# LAMEBOY.net
KiCad netlist of a schematic drawn in EAGLE
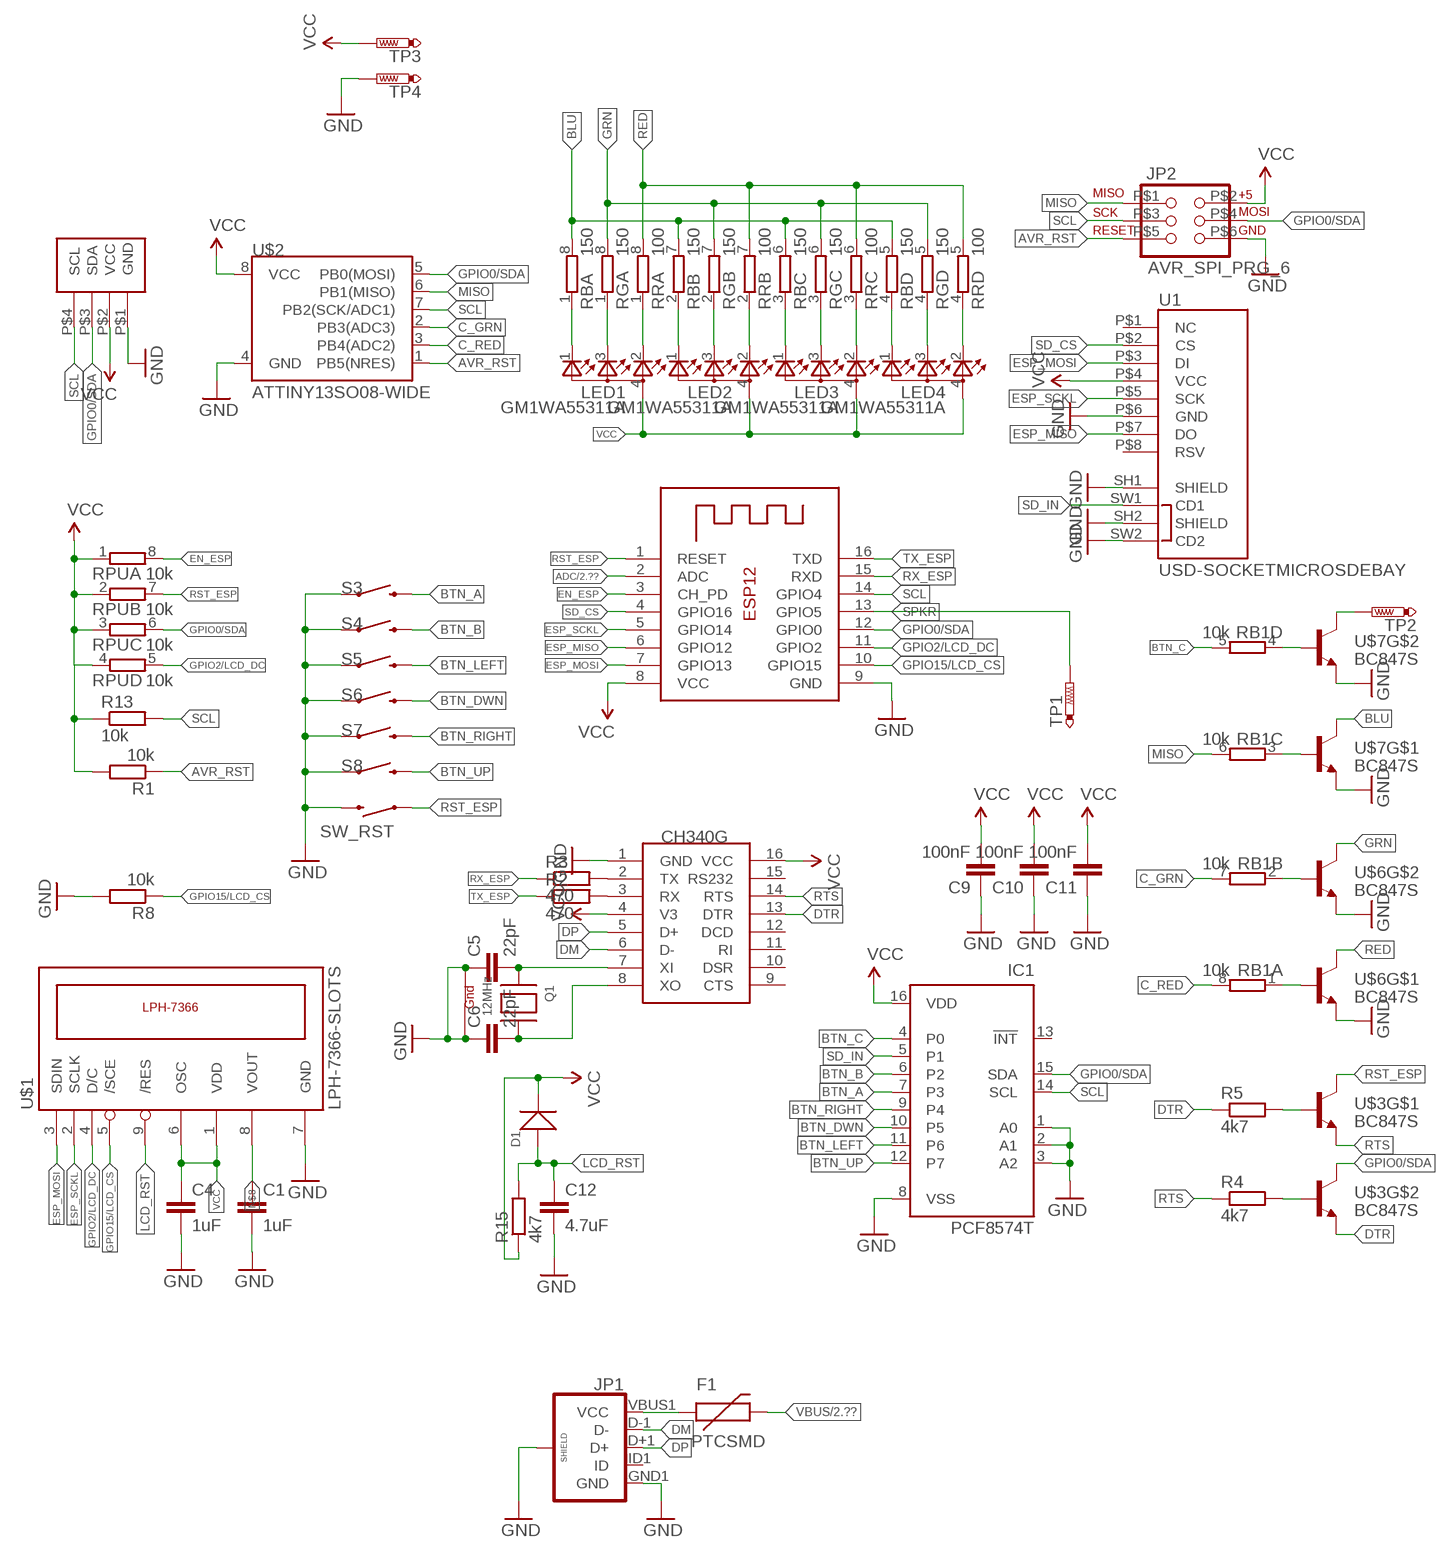
[diagram p0: schematic, sheet 1]
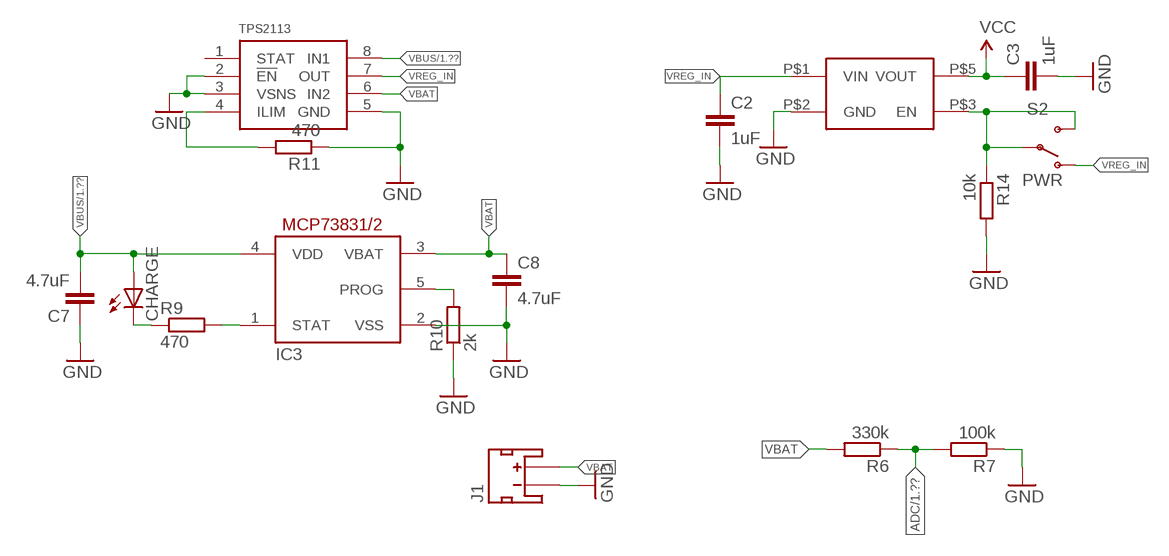
[diagram p1: schematic, sheet 2]

(export (version "E")
  (design (tool "Eeschema 10.0.6"))
  (components
    (comp (ref "C1")
      (value "1uF")
      (footprint "eagle-import:C0805")
      (libsource (lib "eagle-import") (part "C-EUC0805"))
    )
    (comp (ref "C4")
      (value "1uF")
      (footprint "eagle-import:C0805")
      (libsource (lib "eagle-import") (part "C-EUC0805"))
    )
    (comp (ref "C5")
      (value "22pF")
      (footprint "eagle-import:C0805")
      (libsource (lib "eagle-import") (part "C-EUC0805"))
    )
    (comp (ref "C6")
      (value "22pF")
      (footprint "eagle-import:C0805")
      (libsource (lib "eagle-import") (part "C-EUC0805"))
    )
    (comp (ref "C9")
      (value "100nF")
      (footprint "eagle-import:C0805")
      (libsource (lib "eagle-import") (part "C-EUC0805"))
    )
    (comp (ref "C10")
      (value "100nF")
      (footprint "eagle-import:C0805")
      (libsource (lib "eagle-import") (part "C-EUC0805"))
    )
    (comp (ref "C11")
      (value "100nF")
      (footprint "eagle-import:C0805")
      (libsource (lib "eagle-import") (part "C-EUC0805"))
    )
    (comp (ref "C12")
      (value "4.7uF")
      (footprint "eagle-import:C0805")
      (libsource (lib "eagle-import") (part "C-EUC0805"))
    )
    (comp (ref "CH340G")
      (value "CH340GCH340G")
      (footprint "eagle-import:SOIC16")
      (libsource (lib "eagle-import") (part "CH340GCH340G"))
    )
    (comp (ref "D1")
      (value "DIODE'1N4148-SMD'")
      (footprint "eagle-import:LL-34")
      (libsource (lib "eagle-import") (part "DIODE'1N4148-SMD'"))
    )
    (comp (ref "F1")
      (value "PTCSMD")
      (footprint "eagle-import:PTC-1206")
      (libsource (lib "eagle-import") (part "PTCSMD"))
    )
    (comp (ref "IC1")
      (value "PCF8574T")
      (footprint "eagle-import:SO16W")
      (fields (field (name "MPN") "PCF8574T/3,512"))
      (libsource (lib "eagle-import") (part "PCF8574T"))
    )
    (comp (ref "JP1")
      (value "USB_MICROB_PLUG-IDK")
      (footprint "eagle-import:USB-AB-MICRO-SMD_SLOT")
      (libsource (lib "eagle-import") (part "USB_MICROB_PLUG-IDK"))
    )
    (comp (ref "JP2")
      (value "AVR_SPI_PRG_6")
      (footprint "eagle-import:2X3_SMD_PAD")
      (libsource (lib "eagle-import") (part "AVR_SPI_PRG_6"))
    )
    (comp (ref "LED1")
      (value "GM1WA55311A")
      (footprint "eagle-import:GM1WA55311A")
      (libsource (lib "eagle-import") (part "GM1WA55311A"))
    )
    (comp (ref "LED2")
      (value "GM1WA55311A")
      (footprint "eagle-import:GM1WA55311A")
      (libsource (lib "eagle-import") (part "GM1WA55311A"))
    )
    (comp (ref "LED3")
      (value "GM1WA55311A")
      (footprint "eagle-import:GM1WA55311A")
      (libsource (lib "eagle-import") (part "GM1WA55311A"))
    )
    (comp (ref "LED4")
      (value "GM1WA55311A")
      (footprint "eagle-import:GM1WA55311A")
      (libsource (lib "eagle-import") (part "GM1WA55311A"))
    )
    (comp (ref "Q1")
      (value "12MHz")
      (footprint "eagle-import:NX3225_BIGGER")
      (libsource (lib "eagle-import") (part "XTAL-4BIGGER"))
    )
    (comp (ref "R1")
      (value "10k")
      (footprint "eagle-import:R0805")
      (libsource (lib "eagle-import") (part "R-EU_R0805"))
    )
    (comp (ref "R2")
      (value "470")
      (footprint "eagle-import:R0805")
      (libsource (lib "eagle-import") (part "R-EU_R0805"))
    )
    (comp (ref "R3")
      (value "470")
      (footprint "eagle-import:R0805")
      (libsource (lib "eagle-import") (part "R-EU_R0805"))
    )
    (comp (ref "R4")
      (value "4k7")
      (footprint "eagle-import:R0805")
      (libsource (lib "eagle-import") (part "R-EU_R0805"))
    )
    (comp (ref "R5")
      (value "4k7")
      (footprint "eagle-import:R0805")
      (libsource (lib "eagle-import") (part "R-EU_R0805"))
    )
    (comp (ref "R8")
      (value "10k")
      (footprint "eagle-import:R0805")
      (libsource (lib "eagle-import") (part "R-EU_R0805"))
    )
    (comp (ref "R13")
      (value "10k")
      (footprint "eagle-import:R0805")
      (libsource (lib "eagle-import") (part "R-EU_R0805"))
    )
    (comp (ref "R15")
      (value "4k7")
      (footprint "eagle-import:R0805")
      (libsource (lib "eagle-import") (part "R-EU_R0805"))
    )
    (comp (ref "RB")
      (value "150")
      (footprint "eagle-import:0603-ARC")
      (libsource (lib "eagle-import") (part "4R-N0603-ARC"))
    )
    (comp (ref "RB1")
      (value "10k")
      (footprint "eagle-import:0603-ARC")
      (libsource (lib "eagle-import") (part "4R-N0603-ARC"))
    )
    (comp (ref "RG")
      (value "150")
      (footprint "eagle-import:0603-ARC")
      (libsource (lib "eagle-import") (part "4R-N0603-ARC"))
    )
    (comp (ref "RPU")
      (value "10k")
      (footprint "eagle-import:0603-ARC")
      (libsource (lib "eagle-import") (part "4R-N0603-ARC"))
    )
    (comp (ref "RR")
      (value "100")
      (footprint "eagle-import:0603-ARC")
      (libsource (lib "eagle-import") (part "4R-N0603-ARC"))
    )
    (comp (ref "S3")
      (value "SWITCH-MOMENTARY-2SMD-4")
      (footprint "eagle-import:TACTILE_SWITCH_TALL")
      (libsource (lib "eagle-import") (part "SWITCH-MOMENTARY-2SMD-4"))
    )
    (comp (ref "S4")
      (value "SWITCH-MOMENTARY-2SMD-4")
      (footprint "eagle-import:TACTILE_SWITCH_TALL")
      (libsource (lib "eagle-import") (part "SWITCH-MOMENTARY-2SMD-4"))
    )
    (comp (ref "S5")
      (value "SWITCH-MOMENTARY-2SMD-4")
      (footprint "eagle-import:TACTILE_SWITCH_TALL")
      (libsource (lib "eagle-import") (part "SWITCH-MOMENTARY-2SMD-4"))
    )
    (comp (ref "S6")
      (value "SWITCH-MOMENTARY-2SMD-4")
      (footprint "eagle-import:TACTILE_SWITCH_TALL")
      (libsource (lib "eagle-import") (part "SWITCH-MOMENTARY-2SMD-4"))
    )
    (comp (ref "S7")
      (value "SWITCH-MOMENTARY-2SMD-4")
      (footprint "eagle-import:TACTILE_SWITCH_TALL")
      (libsource (lib "eagle-import") (part "SWITCH-MOMENTARY-2SMD-4"))
    )
    (comp (ref "S8")
      (value "SWITCH-MOMENTARY-2SMD-4")
      (footprint "eagle-import:TACTILE_SWITCH_TALL")
      (libsource (lib "eagle-import") (part "SWITCH-MOMENTARY-2SMD-4"))
    )
    (comp (ref "SW_RST")
      (value "SWITCH-MOMENTARY-2-SMD-1101NE")
      (footprint "eagle-import:TACTILE-SWITCH-1101NE")
      (libsource (lib "eagle-import") (part "SWITCH-MOMENTARY-2-SMD-1101NE"))
    )
    (comp (ref "TP1")
      (value "PTR1B1,27")
      (footprint "eagle-import:B1,27")
      (libsource (lib "eagle-import") (part "PTR1B1,27"))
    )
    (comp (ref "TP2")
      (value "PTR1B1,27")
      (footprint "eagle-import:B1,27")
      (libsource (lib "eagle-import") (part "PTR1B1,27"))
    )
    (comp (ref "TP3")
      (value "PTR1B1,27")
      (footprint "eagle-import:B1,27")
      (libsource (lib "eagle-import") (part "PTR1B1,27"))
    )
    (comp (ref "TP4")
      (value "PTR1B1,27")
      (footprint "eagle-import:B1,27")
      (libsource (lib "eagle-import") (part "PTR1B1,27"))
    )
    (comp (ref "U$1")
      (value "LPH-7366-SLOTS")
      (footprint "eagle-import:LPH-7366-SLOTS")
      (libsource (lib "eagle-import") (part "LPH-7366-SLOTS"))
    )
    (comp (ref "U$2")
      (value "ATTINY13SO08-WIDE")
      (footprint "eagle-import:SO08-EIAJ")
      (libsource (lib "eagle-import") (part "ATTINY13SO08-WIDE"))
    )
    (comp (ref "U$3")
      (value "BC847S")
      (footprint "eagle-import:SOT363")
      (libsource (lib "eagle-import") (part "MMDT3904"))
    )
    (comp (ref "U$6")
      (value "BC847S")
      (footprint "eagle-import:SOT363")
      (libsource (lib "eagle-import") (part "MMDT3904"))
    )
    (comp (ref "U$7")
      (value "BC847S")
      (footprint "eagle-import:SOT363")
      (libsource (lib "eagle-import") (part "MMDT3904"))
    )
    (comp (ref "U$10")
      (value "I2C_GROVE")
      (footprint "eagle-import:I2C_GROVE")
      (libsource (lib "eagle-import") (part "I2C_GROVE"))
    )
    (comp (ref "U1")
      (value "USD-SOCKETMICROSDEBAY")
      (footprint "eagle-import:MICRO-SD-SOCKET-EBAY")
      (libsource (lib "eagle-import") (part "USD-SOCKETMICROSDEBAY"))
    )
    (comp (ref "X1")
      (value "ESP-12")
      (footprint "eagle-import:ESP-12")
      (libsource (lib "eagle-import") (part "ESP-12"))
    )
    (comp (ref "C2")
      (value "1uF")
      (footprint "eagle-import:C0805")
      (libsource (lib "eagle-import") (part "C-EUC0805"))
    )
    (comp (ref "C3")
      (value "1uF")
      (footprint "eagle-import:C0805")
      (libsource (lib "eagle-import") (part "C-EUC0805"))
    )
    (comp (ref "C7")
      (value "4.7uF")
      (footprint "eagle-import:C0805")
      (libsource (lib "eagle-import") (part "C-EUC0805"))
    )
    (comp (ref "C8")
      (value "4.7uF")
      (footprint "eagle-import:C0805")
      (libsource (lib "eagle-import") (part "C-EUC0805"))
    )
    (comp (ref "CHARGE")
      (value "LEDCHARLIE")
      (footprint "eagle-import:CHIPLED_0603_CHARLIE")
      (libsource (lib "eagle-import") (part "LEDCHARLIE"))
    )
    (comp (ref "IC3")
      (value "MCP73831")
      (footprint "eagle-import:SOT23-5L")
      (libsource (lib "eagle-import") (part "MCP73831/OT"))
    )
    (comp (ref "J1")
      (value "JST_2MM_MALE")
      (footprint "eagle-import:JST-2-SMD")
      (libsource (lib "eagle-import") (part "JST_2MM_MALE"))
    )
    (comp (ref "R6")
      (value "330k")
      (footprint "eagle-import:R0805")
      (libsource (lib "eagle-import") (part "R-EU_R0805"))
    )
    (comp (ref "R7")
      (value "100k")
      (footprint "eagle-import:R0805")
      (libsource (lib "eagle-import") (part "R-EU_R0805"))
    )
    (comp (ref "R9")
      (value "470")
      (footprint "eagle-import:R0805")
      (libsource (lib "eagle-import") (part "R-EU_R0805"))
    )
    (comp (ref "R10")
      (value "2k")
      (footprint "eagle-import:R0805")
      (libsource (lib "eagle-import") (part "R-EU_R0805"))
    )
    (comp (ref "R11")
      (value "470")
      (footprint "eagle-import:R0805")
      (libsource (lib "eagle-import") (part "R-EU_R0805"))
    )
    (comp (ref "R14")
      (value "10k")
      (footprint "eagle-import:R0805")
      (libsource (lib "eagle-import") (part "R-EU_R0805"))
    )
    (comp (ref "S2")
      (value "PWR")
      (footprint "eagle-import:SWITCH-SPST-SMD-A")
      (libsource (lib "eagle-import") (part "SWITCH-SPDT-SMD-A"))
    )
    (comp (ref "U$4")
      (value "TPS2113-PW")
      (footprint "eagle-import:TEXAS-PW")
      (libsource (lib "eagle-import") (part "TPS2113-PW"))
    )
    (comp (ref "U$9")
      (value "AP2112KAP2112K")
      (footprint "eagle-import:AP2112")
      (libsource (lib "eagle-import") (part "AP2112KAP2112K"))
    )
  )
  (nets
    (net (code "1") (name "ADC") (class "Default")
      (node (ref "R6") (pin "1") (pinfunction "1_1") (pintype "passive"))
      (node (ref "R7") (pin "2") (pinfunction "2_2") (pintype "passive"))
      (node (ref "X1") (pin "2") (pinfunction "ADC_2") (pintype "passive"))
    )
    (net (code "2") (name "AVR_RST") (class "Default")
      (node (ref "JP2") (pin "P$5") (pinfunction "5_P$5") (pintype "passive"))
      (node (ref "R1") (pin "1") (pinfunction "1_1") (pintype "passive"))
      (node (ref "U$2") (pin "1") (pinfunction "PB5(NRES)_1") (pintype "bidirectional"))
    )
    (net (code "3") (name "BLU") (class "Default")
      (node (ref "RB") (pin "5") (pinfunction "2_5") (pintype "passive"))
      (node (ref "RB") (pin "6") (pinfunction "2_6") (pintype "passive"))
      (node (ref "RB") (pin "7") (pinfunction "2_7") (pintype "passive"))
      (node (ref "RB") (pin "8") (pinfunction "2_8") (pintype "passive"))
      (node (ref "U$7") (pin "3") (pinfunction "C_3") (pintype "passive"))
    )
    (net (code "4") (name "BTN_A") (class "Default")
      (node (ref "IC1") (pin "7") (pinfunction "P3_7") (pintype "bidirectional"))
      (node (ref "S3") (pin "B2") (pinfunction "2_B2") (pintype "passive"))
    )
    (net (code "5") (name "BTN_B") (class "Default")
      (node (ref "IC1") (pin "6") (pinfunction "P2_6") (pintype "bidirectional"))
      (node (ref "S4") (pin "B2") (pinfunction "2_B2") (pintype "passive"))
    )
    (net (code "6") (name "BTN_C") (class "Default")
      (node (ref "IC1") (pin "4") (pinfunction "P0_4") (pintype "bidirectional"))
      (node (ref "RB1") (pin "5") (pinfunction "2_5") (pintype "passive"))
    )
    (net (code "7") (name "BTN_DWN") (class "Default")
      (node (ref "IC1") (pin "10") (pinfunction "P5_10") (pintype "bidirectional"))
      (node (ref "S6") (pin "B2") (pinfunction "2_B2") (pintype "passive"))
    )
    (net (code "8") (name "BTN_LEFT") (class "Default")
      (node (ref "IC1") (pin "11") (pinfunction "P6_11") (pintype "bidirectional"))
      (node (ref "S5") (pin "B2") (pinfunction "2_B2") (pintype "passive"))
    )
    (net (code "9") (name "BTN_RIGHT") (class "Default")
      (node (ref "IC1") (pin "9") (pinfunction "P4_9") (pintype "bidirectional"))
      (node (ref "S7") (pin "B2") (pinfunction "2_B2") (pintype "passive"))
    )
    (net (code "10") (name "BTN_UP") (class "Default")
      (node (ref "IC1") (pin "12") (pinfunction "P7_12") (pintype "bidirectional"))
      (node (ref "S8") (pin "B2") (pinfunction "2_B2") (pintype "passive"))
    )
    (net (code "11") (name "C_GRN") (class "Default")
      (node (ref "RB1") (pin "7") (pinfunction "2_7") (pintype "passive"))
      (node (ref "U$2") (pin "2") (pinfunction "PB3(ADC3)_2") (pintype "bidirectional"))
    )
    (net (code "12") (name "C_RED") (class "Default")
      (node (ref "RB1") (pin "8") (pinfunction "2_8") (pintype "passive"))
      (node (ref "U$2") (pin "3") (pinfunction "PB4(ADC2)_3") (pintype "bidirectional"))
    )
    (net (code "13") (name "DM") (class "Default")
      (node (ref "CH340G") (pin "6") (pinfunction "D-_6") (pintype "bidirectional"))
      (node (ref "JP1") (pin "D-1") (pinfunction "D-_D-1") (pintype "bidirectional"))
    )
    (net (code "14") (name "DP") (class "Default")
      (node (ref "CH340G") (pin "5") (pinfunction "D+_5") (pintype "bidirectional"))
      (node (ref "JP1") (pin "D+1") (pinfunction "D+_D+1") (pintype "bidirectional"))
    )
    (net (code "15") (name "DTR") (class "Default")
      (node (ref "CH340G") (pin "13") (pinfunction "DTR_13") (pintype "bidirectional"))
      (node (ref "R5") (pin "1") (pinfunction "1_1") (pintype "passive"))
      (node (ref "U$3") (pin "1") (pinfunction "E_1") (pintype "passive"))
    )
    (net (code "16") (name "EN_ESP") (class "Default")
      (node (ref "RPU") (pin "8") (pinfunction "2_8") (pintype "passive"))
      (node (ref "X1") (pin "3") (pinfunction "CH_PD_3") (pintype "input"))
    )
    (net (code "17") (name "ESP_MISO") (class "Default")
      (node (ref "U1") (pin "P$7") (pinfunction "DO_P$7") (pintype "bidirectional"))
      (node (ref "X1") (pin "6") (pinfunction "GPIO12_6") (pintype "bidirectional"))
    )
    (net (code "18") (name "ESP_MOSI") (class "Default")
      (node (ref "U$1") (pin "3") (pinfunction "SDIN_3") (pintype "input"))
      (node (ref "U1") (pin "P$3") (pinfunction "DI_P$3") (pintype "bidirectional"))
      (node (ref "X1") (pin "7") (pinfunction "GPIO13_7") (pintype "bidirectional"))
    )
    (net (code "19") (name "ESP_SCKL") (class "Default")
      (node (ref "U$1") (pin "2") (pinfunction "SCLK_2") (pintype "input"))
      (node (ref "U1") (pin "P$5") (pinfunction "SCK_P$5") (pintype "bidirectional"))
      (node (ref "X1") (pin "5") (pinfunction "GPIO14_5") (pintype "bidirectional"))
    )
    (net (code "20") (name "GND") (class "Default")
      (node (ref "C1") (pin "2") (pinfunction "2_2") (pintype "passive"))
      (node (ref "C10") (pin "1") (pinfunction "1_1") (pintype "passive"))
      (node (ref "C11") (pin "1") (pinfunction "1_1") (pintype "passive"))
      (node (ref "C12") (pin "2") (pinfunction "2_2") (pintype "passive"))
      (node (ref "C2") (pin "2") (pinfunction "2_2") (pintype "passive"))
      (node (ref "C3") (pin "2") (pinfunction "2_2") (pintype "passive"))
      (node (ref "C4") (pin "2") (pinfunction "2_2") (pintype "passive"))
      (node (ref "C5") (pin "1") (pinfunction "1_1") (pintype "passive"))
      (node (ref "C6") (pin "1") (pinfunction "1_1") (pintype "passive"))
      (node (ref "C7") (pin "1") (pinfunction "1_1") (pintype "passive"))
      (node (ref "C8") (pin "2") (pinfunction "2_2") (pintype "passive"))
      (node (ref "C9") (pin "1") (pinfunction "1_1") (pintype "passive"))
      (node (ref "CH340G") (pin "1") (pinfunction "GND_1") (pintype "bidirectional"))
      (node (ref "IC1") (pin "1") (pinfunction "A0_1") (pintype "input"))
      (node (ref "IC1") (pin "2") (pinfunction "A1_2") (pintype "input"))
      (node (ref "IC1") (pin "3") (pinfunction "A2_3") (pintype "input"))
      (node (ref "IC1") (pin "8") (pinfunction "VSS_8") (pintype "power_in"))
      (node (ref "IC3") (pin "2") (pinfunction "VSS_2") (pintype "power_in"))
      (node (ref "J1") (pin "1") (pinfunction "-_1") (pintype "bidirectional"))
      (node (ref "JP1") (pin "GND1") (pinfunction "GND_GND1") (pintype "bidirectional"))
      (node (ref "JP1") (pin "P$1") (pinfunction "SHIELD_P$1") (pintype "bidirectional"))
      (node (ref "JP1") (pin "P$2") (pinfunction "SHIELD_P$2") (pintype "bidirectional"))
      (node (ref "JP1") (pin "P$3") (pinfunction "SHIELD_P$3") (pintype "bidirectional"))
      (node (ref "JP1") (pin "P$4") (pinfunction "SHIELD_P$4") (pintype "bidirectional"))
      (node (ref "JP2") (pin "P$6") (pinfunction "6_P$6") (pintype "passive"))
      (node (ref "Q1") (pin "2") (pinfunction "G2_2") (pintype "power_in"))
      (node (ref "Q1") (pin "4") (pinfunction "G1_4") (pintype "power_in"))
      (node (ref "R10") (pin "1") (pinfunction "1_1") (pintype "passive"))
      (node (ref "R11") (pin "1") (pinfunction "1_1") (pintype "passive"))
      (node (ref "R14") (pin "2") (pinfunction "2_2") (pintype "passive"))
      (node (ref "R7") (pin "1") (pinfunction "1_1") (pintype "passive"))
      (node (ref "R8") (pin "2") (pinfunction "2_2") (pintype "passive"))
      (node (ref "S3") (pin "A2") (pinfunction "1_A2") (pintype "passive"))
      (node (ref "S4") (pin "A2") (pinfunction "1_A2") (pintype "passive"))
      (node (ref "S5") (pin "A2") (pinfunction "1_A2") (pintype "passive"))
      (node (ref "S6") (pin "A2") (pinfunction "1_A2") (pintype "passive"))
      (node (ref "S7") (pin "A2") (pinfunction "1_A2") (pintype "passive"))
      (node (ref "S8") (pin "A2") (pinfunction "1_A2") (pintype "passive"))
      (node (ref "SW_RST") (pin "P$2") (pinfunction "2_P$2") (pintype "passive"))
      (node (ref "TP4") (pin "TP") (pinfunction "TP_TP") (pintype "input"))
      (node (ref "U$1") (pin "7") (pinfunction "GND_7") (pintype "power_in"))
      (node (ref "U$10") (pin "P$1") (pinfunction "GND_P$1") (pintype "bidirectional"))
      (node (ref "U$2") (pin "4") (pinfunction "GND_4") (pintype "bidirectional"))
      (node (ref "U$4") (pin "2") (pinfunction "~{EN}_2") (pintype "bidirectional"))
      (node (ref "U$4") (pin "3") (pinfunction "VSNS_3") (pintype "bidirectional"))
      (node (ref "U$4") (pin "5") (pinfunction "GND_5") (pintype "bidirectional"))
      (node (ref "U$6") (pin "1") (pinfunction "E_1") (pintype "passive"))
      (node (ref "U$6") (pin "4") (pinfunction "E_4") (pintype "passive"))
      (node (ref "U$7") (pin "1") (pinfunction "E_1") (pintype "passive"))
      (node (ref "U$7") (pin "4") (pinfunction "E_4") (pintype "passive"))
      (node (ref "U$9") (pin "P$2") (pinfunction "GND_P$2") (pintype "bidirectional"))
      (node (ref "U1") (pin "P$6") (pinfunction "GND_P$6") (pintype "bidirectional"))
      (node (ref "U1") (pin "SH1") (pinfunction "SHIELD_SH1") (pintype "bidirectional"))
      (node (ref "U1") (pin "SH2") (pinfunction "SHIELD_SH2") (pintype "bidirectional"))
      (node (ref "U1") (pin "SW2") (pinfunction "CD2_SW2") (pintype "bidirectional"))
      (node (ref "X1") (pin "9") (pinfunction "GND_9") (pintype "power_in"))
    )
    (net (code "21") (name "GPIO0{slash}SDA") (class "Default")
      (node (ref "IC1") (pin "15") (pinfunction "SDA_15") (pintype "bidirectional"))
      (node (ref "JP2") (pin "P$4") (pinfunction "4_P$4") (pintype "passive"))
      (node (ref "RPU") (pin "6") (pinfunction "2_6") (pintype "passive"))
      (node (ref "U$10") (pin "P$3") (pinfunction "SDA_P$3") (pintype "bidirectional"))
      (node (ref "U$2") (pin "5") (pinfunction "PB0(MOSI)_5") (pintype "bidirectional"))
      (node (ref "U$3") (pin "6") (pinfunction "C_6") (pintype "passive"))
      (node (ref "X1") (pin "12") (pinfunction "GPIO0_12") (pintype "bidirectional"))
    )
    (net (code "22") (name "GPIO2{slash}LCD_DC") (class "Default")
      (node (ref "RPU") (pin "5") (pinfunction "2_5") (pintype "passive"))
      (node (ref "U$1") (pin "4") (pinfunction "D/C_4") (pintype "input"))
      (node (ref "X1") (pin "11") (pinfunction "GPIO2_11") (pintype "bidirectional"))
    )
    (net (code "23") (name "GPIO15{slash}LCD_CS") (class "Default")
      (node (ref "R8") (pin "1") (pinfunction "1_1") (pintype "passive"))
      (node (ref "U$1") (pin "5") (pinfunction "/SCE_5") (pintype "input"))
      (node (ref "X1") (pin "10") (pinfunction "GPIO15_10") (pintype "bidirectional"))
    )
    (net (code "24") (name "GRN") (class "Default")
      (node (ref "RG") (pin "5") (pinfunction "2_5") (pintype "passive"))
      (node (ref "RG") (pin "6") (pinfunction "2_6") (pintype "passive"))
      (node (ref "RG") (pin "7") (pinfunction "2_7") (pintype "passive"))
      (node (ref "RG") (pin "8") (pinfunction "2_8") (pintype "passive"))
      (node (ref "U$6") (pin "6") (pinfunction "C_6") (pintype "passive"))
    )
    (net (code "25") (name "LCD_RST") (class "Default")
      (node (ref "C12") (pin "1") (pinfunction "1_1") (pintype "passive"))
      (node (ref "D1") (pin "A") (pinfunction "+_A") (pintype "passive"))
      (node (ref "R15") (pin "2") (pinfunction "2_2") (pintype "passive"))
      (node (ref "U$1") (pin "9") (pinfunction "/RES_9") (pintype "input"))
    )
    (net (code "26") (name "MISO") (class "Default")
      (node (ref "JP2") (pin "P$1") (pinfunction "1_P$1") (pintype "passive"))
      (node (ref "RB1") (pin "6") (pinfunction "2_6") (pintype "passive"))
      (node (ref "U$2") (pin "6") (pinfunction "PB1(MISO)_6") (pintype "bidirectional"))
    )
    (net (code "27") (name "N$8") (class "Default")
      (node (ref "C1") (pin "1") (pinfunction "1_1") (pintype "passive"))
      (node (ref "U$1") (pin "8") (pinfunction "VOUT_8") (pintype "passive"))
    )
    (net (code "28") (name "Net-(CH340G-RX)") (class "Default")
      (node (ref "CH340G") (pin "3") (pinfunction "RX_3") (pintype "bidirectional"))
      (node (ref "R2") (pin "2") (pinfunction "2_2") (pintype "passive"))
    )
    (net (code "29") (name "Net-(CH340G-TX)") (class "Default")
      (node (ref "CH340G") (pin "2") (pinfunction "TX_2") (pintype "bidirectional"))
      (node (ref "R3") (pin "2") (pinfunction "2_2") (pintype "passive"))
    )
    (net (code "30") (name "Net-(CH340G-XI)") (class "Default")
      (node (ref "C5") (pin "2") (pinfunction "2_2") (pintype "passive"))
      (node (ref "CH340G") (pin "7") (pinfunction "XI_7") (pintype "bidirectional"))
      (node (ref "Q1") (pin "1") (pinfunction "X1_1") (pintype "bidirectional"))
    )
    (net (code "31") (name "Net-(CH340G-XO)") (class "Default")
      (node (ref "C6") (pin "2") (pinfunction "2_2") (pintype "passive"))
      (node (ref "CH340G") (pin "8") (pinfunction "XO_8") (pintype "bidirectional"))
      (node (ref "Q1") (pin "3") (pinfunction "X2_3") (pintype "bidirectional"))
    )
    (net (code "32") (name "Net-(CHARGE-PadC)") (class "Default")
      (node (ref "CHARGE") (pin "C") (pinfunction "C_C") (pintype "passive"))
      (node (ref "R9") (pin "1") (pinfunction "1_1") (pintype "passive"))
    )
    (net (code "33") (name "Net-(IC3-PROG)") (class "Default")
      (node (ref "IC3") (pin "5") (pinfunction "PROG_5") (pintype "input"))
      (node (ref "R10") (pin "2") (pinfunction "2_2") (pintype "passive"))
    )
    (net (code "34") (name "Net-(IC3-STAT)") (class "Default")
      (node (ref "IC3") (pin "1") (pinfunction "STAT_1") (pintype "output"))
      (node (ref "R9") (pin "2") (pinfunction "2_2") (pintype "passive"))
    )
    (net (code "35") (name "Net-(JP1-VCC)") (class "Default")
      (node (ref "F1") (pin "1") (pinfunction "1_1") (pintype "bidirectional"))
      (node (ref "JP1") (pin "VBUS1") (pinfunction "VCC_VBUS1") (pintype "bidirectional"))
    )
    (net (code "36") (name "Net-(LED1-CBLUE)") (class "Default")
      (node (ref "LED1") (pin "3") (pinfunction "CBLUE_3") (pintype "passive"))
      (node (ref "RG") (pin "1") (pinfunction "1_1") (pintype "passive"))
    )
    (net (code "37") (name "Net-(LED1-CGREEN)") (class "Default")
      (node (ref "LED1") (pin "1") (pinfunction "CGREEN_1") (pintype "passive"))
      (node (ref "RB") (pin "1") (pinfunction "1_1") (pintype "passive"))
    )
    (net (code "38") (name "Net-(LED1-CRED)") (class "Default")
      (node (ref "LED1") (pin "2") (pinfunction "CRED_2") (pintype "passive"))
      (node (ref "RR") (pin "1") (pinfunction "1_1") (pintype "passive"))
    )
    (net (code "39") (name "Net-(LED2-CBLUE)") (class "Default")
      (node (ref "LED2") (pin "3") (pinfunction "CBLUE_3") (pintype "passive"))
      (node (ref "RG") (pin "2") (pinfunction "1_2") (pintype "passive"))
    )
    (net (code "40") (name "Net-(LED2-CGREEN)") (class "Default")
      (node (ref "LED2") (pin "1") (pinfunction "CGREEN_1") (pintype "passive"))
      (node (ref "RB") (pin "2") (pinfunction "1_2") (pintype "passive"))
    )
    (net (code "41") (name "Net-(LED2-CRED)") (class "Default")
      (node (ref "LED2") (pin "2") (pinfunction "CRED_2") (pintype "passive"))
      (node (ref "RR") (pin "2") (pinfunction "1_2") (pintype "passive"))
    )
    (net (code "42") (name "Net-(LED3-CBLUE)") (class "Default")
      (node (ref "LED3") (pin "3") (pinfunction "CBLUE_3") (pintype "passive"))
      (node (ref "RG") (pin "3") (pinfunction "1_3") (pintype "passive"))
    )
    (net (code "43") (name "Net-(LED3-CGREEN)") (class "Default")
      (node (ref "LED3") (pin "1") (pinfunction "CGREEN_1") (pintype "passive"))
      (node (ref "RB") (pin "3") (pinfunction "1_3") (pintype "passive"))
    )
    (net (code "44") (name "Net-(LED3-CRED)") (class "Default")
      (node (ref "LED3") (pin "2") (pinfunction "CRED_2") (pintype "passive"))
      (node (ref "RR") (pin "3") (pinfunction "1_3") (pintype "passive"))
    )
    (net (code "45") (name "Net-(LED4-CBLUE)") (class "Default")
      (node (ref "LED4") (pin "3") (pinfunction "CBLUE_3") (pintype "passive"))
      (node (ref "RG") (pin "4") (pinfunction "1_4") (pintype "passive"))
    )
    (net (code "46") (name "Net-(LED4-CGREEN)") (class "Default")
      (node (ref "LED4") (pin "1") (pinfunction "CGREEN_1") (pintype "passive"))
      (node (ref "RB") (pin "4") (pinfunction "1_4") (pintype "passive"))
    )
    (net (code "47") (name "Net-(LED4-CRED)") (class "Default")
      (node (ref "LED4") (pin "2") (pinfunction "CRED_2") (pintype "passive"))
      (node (ref "RR") (pin "4") (pinfunction "1_4") (pintype "passive"))
    )
    (net (code "48") (name "Net-(RB1B-1)") (class "Default")
      (node (ref "RB1") (pin "2") (pinfunction "1_2") (pintype "passive"))
      (node (ref "U$6") (pin "2") (pinfunction "B_2") (pintype "passive"))
    )
    (net (code "49") (name "Net-(RB1C-1)") (class "Default")
      (node (ref "RB1") (pin "3") (pinfunction "1_3") (pintype "passive"))
      (node (ref "U$7") (pin "5") (pinfunction "B_5") (pintype "passive"))
    )
    (net (code "50") (name "Net-(RB1D-1)") (class "Default")
      (node (ref "RB1") (pin "4") (pinfunction "1_4") (pintype "passive"))
      (node (ref "U$7") (pin "2") (pinfunction "B_2") (pintype "passive"))
    )
    (net (code "51") (name "Net-(S2-P)") (class "Default")
      (node (ref "R14") (pin "1") (pinfunction "1_1") (pintype "passive"))
      (node (ref "S2") (pin "2") (pinfunction "P_2") (pintype "passive"))
      (node (ref "S2") (pin "3") (pinfunction "S_3") (pintype "passive"))
      (node (ref "U$9") (pin "P$3") (pinfunction "EN_P$3") (pintype "bidirectional"))
    )
    (net (code "52") (name "Net-(U$3A-B)") (class "Default")
      (node (ref "R5") (pin "2") (pinfunction "2_2") (pintype "passive"))
      (node (ref "U$3") (pin "5") (pinfunction "B_5") (pintype "passive"))
    )
    (net (code "53") (name "Net-(U$3B-B)") (class "Default")
      (node (ref "R4") (pin "2") (pinfunction "2_2") (pintype "passive"))
      (node (ref "U$3") (pin "2") (pinfunction "B_2") (pintype "passive"))
    )
    (net (code "54") (name "Net-(U$4-ILIM)") (class "Default")
      (node (ref "R11") (pin "2") (pinfunction "2_2") (pintype "passive"))
      (node (ref "U$4") (pin "4") (pinfunction "ILIM_4") (pintype "bidirectional"))
    )
    (net (code "55") (name "Net-(U$6A-B)") (class "Default")
      (node (ref "RB1") (pin "1") (pinfunction "1_1") (pintype "passive"))
      (node (ref "U$6") (pin "5") (pinfunction "B_5") (pintype "passive"))
    )
    (net (code "56") (name "Net-(U$7B-C)") (class "Default")
      (node (ref "TP2") (pin "TP") (pinfunction "TP_TP") (pintype "input"))
      (node (ref "U$7") (pin "6") (pinfunction "C_6") (pintype "passive"))
    )
    (net (code "57") (name "RED") (class "Default")
      (node (ref "RR") (pin "5") (pinfunction "2_5") (pintype "passive"))
      (node (ref "RR") (pin "6") (pinfunction "2_6") (pintype "passive"))
      (node (ref "RR") (pin "7") (pinfunction "2_7") (pintype "passive"))
      (node (ref "RR") (pin "8") (pinfunction "2_8") (pintype "passive"))
      (node (ref "U$6") (pin "3") (pinfunction "C_3") (pintype "passive"))
    )
    (net (code "58") (name "RST_ESP") (class "Default")
      (node (ref "RPU") (pin "7") (pinfunction "2_7") (pintype "passive"))
      (node (ref "SW_RST") (pin "P$1") (pinfunction "1_P$1") (pintype "passive"))
      (node (ref "U$3") (pin "3") (pinfunction "C_3") (pintype "passive"))
      (node (ref "X1") (pin "1") (pinfunction "RESET_1") (pintype "input"))
    )
    (net (code "59") (name "RTS") (class "Default")
      (node (ref "CH340G") (pin "14") (pinfunction "RTS_14") (pintype "bidirectional"))
      (node (ref "R4") (pin "1") (pinfunction "1_1") (pintype "passive"))
      (node (ref "U$3") (pin "4") (pinfunction "E_4") (pintype "passive"))
    )
    (net (code "60") (name "RX_ESP") (class "Default")
      (node (ref "R3") (pin "1") (pinfunction "1_1") (pintype "passive"))
      (node (ref "X1") (pin "15") (pinfunction "RXD_15") (pintype "input"))
    )
    (net (code "61") (name "SCL") (class "Default")
      (node (ref "IC1") (pin "14") (pinfunction "SCL_14") (pintype "input"))
      (node (ref "JP2") (pin "P$3") (pinfunction "3_P$3") (pintype "passive"))
      (node (ref "R13") (pin "2") (pinfunction "2_2") (pintype "passive"))
      (node (ref "U$10") (pin "P$4") (pinfunction "SCL_P$4") (pintype "bidirectional"))
      (node (ref "U$2") (pin "7") (pinfunction "PB2(SCK/ADC1)_7") (pintype "bidirectional"))
      (node (ref "X1") (pin "14") (pinfunction "GPIO4_14") (pintype "bidirectional"))
    )
    (net (code "62") (name "SD_CS") (class "Default")
      (node (ref "U1") (pin "P$2") (pinfunction "CS_P$2") (pintype "bidirectional"))
      (node (ref "X1") (pin "4") (pinfunction "GPIO16_4") (pintype "bidirectional"))
    )
    (net (code "63") (name "SD_IN") (class "Default")
      (node (ref "IC1") (pin "5") (pinfunction "P1_5") (pintype "bidirectional"))
      (node (ref "U1") (pin "SW1") (pinfunction "CD1_SW1") (pintype "bidirectional"))
    )
    (net (code "64") (name "SPKR") (class "Default")
      (node (ref "TP1") (pin "TP") (pinfunction "TP_TP") (pintype "input"))
      (node (ref "X1") (pin "13") (pinfunction "GPIO5_13") (pintype "bidirectional"))
    )
    (net (code "65") (name "TX_ESP") (class "Default")
      (node (ref "R2") (pin "1") (pinfunction "1_1") (pintype "passive"))
      (node (ref "X1") (pin "16") (pinfunction "TXD_16") (pintype "output"))
    )
    (net (code "66") (name "VBAT") (class "Default")
      (node (ref "C8") (pin "1") (pinfunction "1_1") (pintype "passive"))
      (node (ref "IC3") (pin "3") (pinfunction "VBAT_3") (pintype "bidirectional"))
      (node (ref "J1") (pin "2") (pinfunction "+_2") (pintype "bidirectional"))
      (node (ref "R6") (pin "2") (pinfunction "2_2") (pintype "passive"))
      (node (ref "U$4") (pin "6") (pinfunction "IN2_6") (pintype "bidirectional"))
    )
    (net (code "67") (name "VBUS") (class "Default")
      (node (ref "C7") (pin "2") (pinfunction "2_2") (pintype "passive"))
      (node (ref "CHARGE") (pin "A") (pinfunction "A_A") (pintype "passive"))
      (node (ref "F1") (pin "2") (pinfunction "2_2") (pintype "bidirectional"))
      (node (ref "IC3") (pin "4") (pinfunction "VDD_4") (pintype "power_in"))
      (node (ref "U$4") (pin "8") (pinfunction "IN1_8") (pintype "bidirectional"))
    )
    (net (code "68") (name "VCC") (class "Default")
      (node (ref "C10") (pin "2") (pinfunction "2_2") (pintype "passive"))
      (node (ref "C11") (pin "2") (pinfunction "2_2") (pintype "passive"))
      (node (ref "C3") (pin "1") (pinfunction "1_1") (pintype "passive"))
      (node (ref "C4") (pin "1") (pinfunction "1_1") (pintype "passive"))
      (node (ref "C9") (pin "2") (pinfunction "2_2") (pintype "passive"))
      (node (ref "CH340G") (pin "16") (pinfunction "VCC_16") (pintype "bidirectional"))
      (node (ref "CH340G") (pin "4") (pinfunction "V3_4") (pintype "bidirectional"))
      (node (ref "D1") (pin "C") (pinfunction "-_C") (pintype "passive"))
      (node (ref "IC1") (pin "16") (pinfunction "VDD_16") (pintype "power_in"))
      (node (ref "JP2") (pin "P$2") (pinfunction "2_P$2") (pintype "passive"))
      (node (ref "LED1") (pin "4") (pinfunction "A_4") (pintype "passive"))
      (node (ref "LED2") (pin "4") (pinfunction "A_4") (pintype "passive"))
      (node (ref "LED3") (pin "4") (pinfunction "A_4") (pintype "passive"))
      (node (ref "LED4") (pin "4") (pinfunction "A_4") (pintype "passive"))
      (node (ref "R1") (pin "2") (pinfunction "2_2") (pintype "passive"))
      (node (ref "R13") (pin "1") (pinfunction "1_1") (pintype "passive"))
      (node (ref "R15") (pin "1") (pinfunction "1_1") (pintype "passive"))
      (node (ref "RPU") (pin "1") (pinfunction "1_1") (pintype "passive"))
      (node (ref "RPU") (pin "2") (pinfunction "1_2") (pintype "passive"))
      (node (ref "RPU") (pin "3") (pinfunction "1_3") (pintype "passive"))
      (node (ref "RPU") (pin "4") (pinfunction "1_4") (pintype "passive"))
      (node (ref "TP3") (pin "TP") (pinfunction "TP_TP") (pintype "input"))
      (node (ref "U$1") (pin "1") (pinfunction "VDD_1") (pintype "power_in"))
      (node (ref "U$1") (pin "6") (pinfunction "OSC_6") (pintype "passive"))
      (node (ref "U$10") (pin "P$2") (pinfunction "VCC_P$2") (pintype "bidirectional"))
      (node (ref "U$2") (pin "8") (pinfunction "VCC_8") (pintype "bidirectional"))
      (node (ref "U$9") (pin "P$5") (pinfunction "VOUT_P$5") (pintype "bidirectional"))
      (node (ref "U1") (pin "P$4") (pinfunction "VCC_P$4") (pintype "bidirectional"))
      (node (ref "X1") (pin "8") (pinfunction "VCC_8") (pintype "power_in"))
    )
    (net (code "69") (name "VREG_IN") (class "Default")
      (node (ref "C2") (pin "1") (pinfunction "1_1") (pintype "passive"))
      (node (ref "S2") (pin "1") (pinfunction "O_1") (pintype "passive"))
      (node (ref "U$4") (pin "7") (pinfunction "OUT_7") (pintype "bidirectional"))
      (node (ref "U$9") (pin "P$1") (pinfunction "VIN_P$1") (pintype "bidirectional"))
    )
    (net (code "70") (name "unconnected-(CH340G-CTS-Pad9)") (class "Default")
      (node (ref "CH340G") (pin "9") (pinfunction "CTS_9") (pintype "bidirectional"))
    )
    (net (code "71") (name "unconnected-(CH340G-DCD-Pad12)") (class "Default")
      (node (ref "CH340G") (pin "12") (pinfunction "DCD_12") (pintype "bidirectional"))
    )
    (net (code "72") (name "unconnected-(CH340G-DSR-Pad10)") (class "Default")
      (node (ref "CH340G") (pin "10") (pinfunction "DSR_10") (pintype "bidirectional"))
    )
    (net (code "73") (name "unconnected-(CH340G-RI-Pad11)") (class "Default")
      (node (ref "CH340G") (pin "11") (pinfunction "RI_11") (pintype "bidirectional"))
    )
    (net (code "74") (name "unconnected-(CH340G-RS232-Pad15)") (class "Default")
      (node (ref "CH340G") (pin "15") (pinfunction "RS232_15") (pintype "bidirectional"))
    )
    (net (code "75") (name "unconnected-(IC1-~{INT}-Pad13)") (class "Default")
      (node (ref "IC1") (pin "13") (pinfunction "~{INT}_13") (pintype "output"))
    )
    (net (code "76") (name "unconnected-(J1-PAD1-PadNC1)") (class "Default")
      (node (ref "J1") (pin "NC1") (pinfunction "PAD1_NC1") (pintype "bidirectional"))
    )
    (net (code "77") (name "unconnected-(J1-PAD2-PadNC2)") (class "Default")
      (node (ref "J1") (pin "NC2") (pinfunction "PAD2_NC2") (pintype "bidirectional"))
    )
    (net (code "78") (name "unconnected-(JP1-ID-PadID1)") (class "Default")
      (node (ref "JP1") (pin "ID1") (pinfunction "ID_ID1") (pintype "bidirectional"))
    )
    (net (code "79") (name "unconnected-(U$4-STAT-Pad1)") (class "Default")
      (node (ref "U$4") (pin "1") (pinfunction "STAT_1") (pintype "bidirectional"))
    )
    (net (code "80") (name "unconnected-(U1-NC-PadP$1)") (class "Default")
      (node (ref "U1") (pin "P$1") (pinfunction "NC_P$1") (pintype "bidirectional"))
    )
    (net (code "81") (name "unconnected-(U1-RSV-PadP$8)") (class "Default")
      (node (ref "U1") (pin "P$8") (pinfunction "RSV_P$8") (pintype "bidirectional"))
    )
  )
)
